# Master.net
KiCad netlist of a schematic drawn in Altium Designer
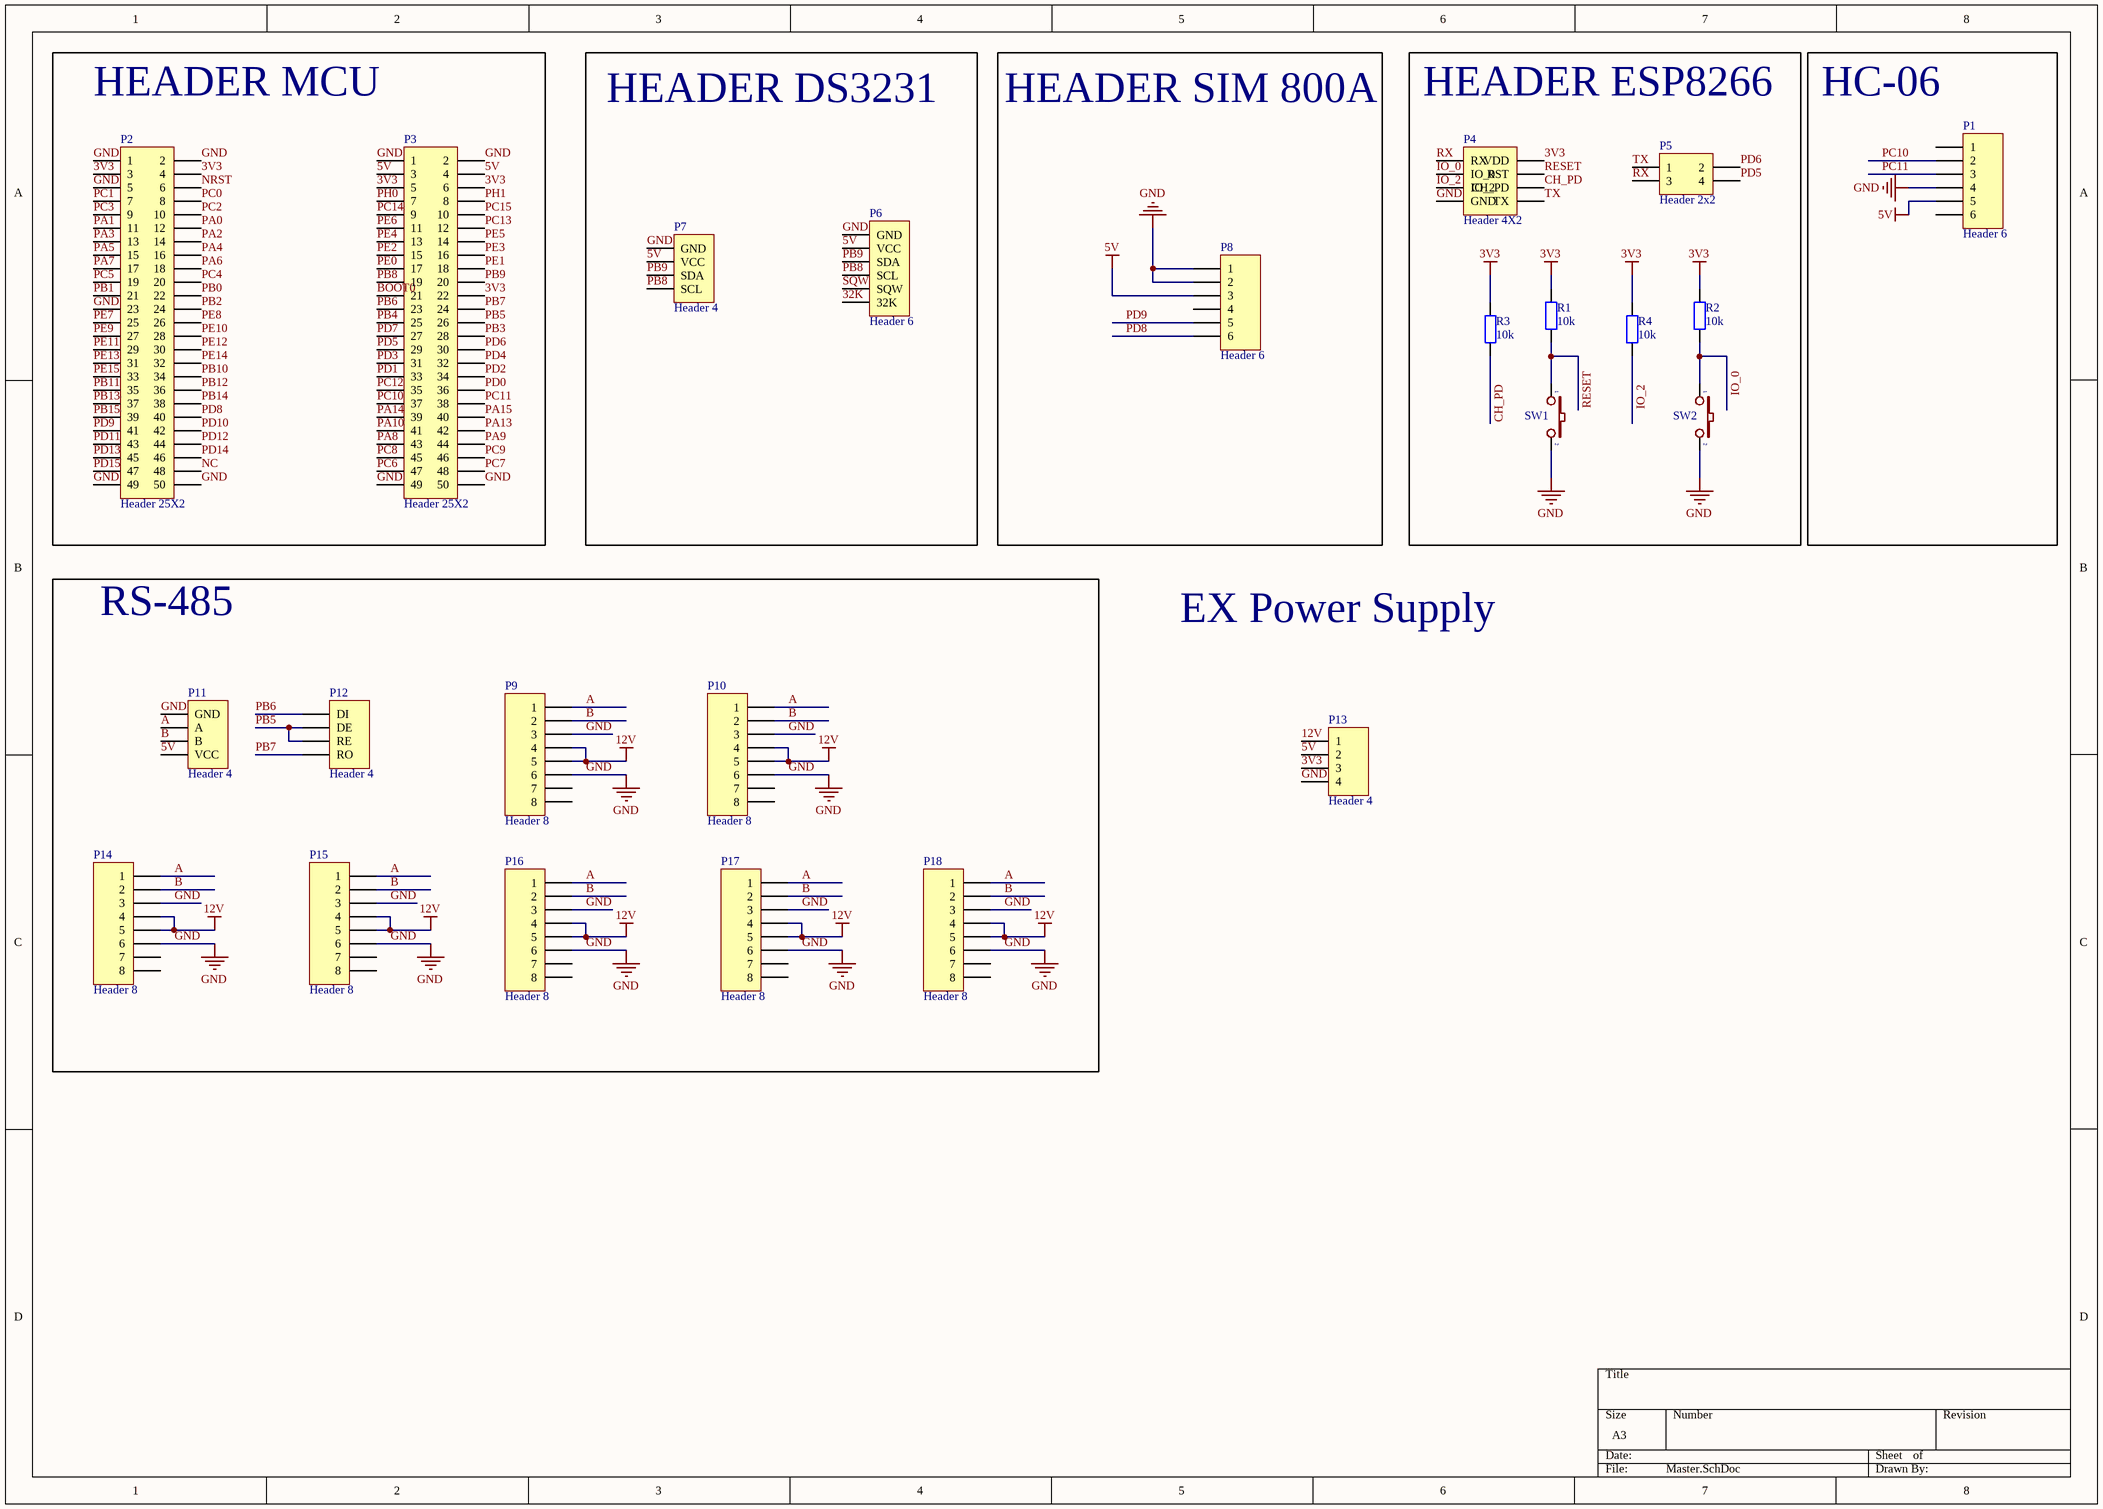
[diagram p0: Master.SchDoc]

(export (version "E")
  (design (tool "Eeschema 10.0.6"))
  (components
    (comp (ref "P1")
      (value "Header 6")
      (footprint "HDR1X6")
      (description "Header, 6-Pin")
      (fields (field (name "PUBLISHER") "Altium Limited"))
      (libsource (lib "THG") (part "Header 6"))
    )
    (comp (ref "P2")
      (value "Header 25X2")
      (footprint "HDR2X25")
      (description "Header, 25-Pin, Dual row")
      (fields (field (name "PUBLISHER") "Altium Limited"))
      (libsource (lib "Miscellaneous Connectors") (part "Header 25X2"))
    )
    (comp (ref "P3")
      (value "Header 25X2")
      (footprint "HDR2X25")
      (description "Header, 25-Pin, Dual row")
      (fields (field (name "PUBLISHER") "Altium Limited"))
      (libsource (lib "Miscellaneous Connectors") (part "Header 25X2"))
    )
    (comp (ref "P4")
      (value "Header 4X2")
      (footprint "HDR2X4")
      (description "Header, 4-Pin, Dual row")
      (fields (field (name "PUBLISHER") "Altium Limited"))
      (libsource (lib "Miscellaneous Connectors") (part "Header 4X2"))
    )
    (comp (ref "P5")
      (value "Header 2x2")
      (footprint "Header 2x2")
      (description "Header, 4-Pin, 2-Row")
      (fields (field (name "PUBLISHER") "Altium Limited"))
      (libsource (lib "hphonglib") (part "Header 2x2"))
    )
    (comp (ref "P6")
      (value "Header 6")
      (footprint "HDR1X6")
      (description "Header, 6-Pin")
      (fields (field (name "PUBLISHER") "Altium Limited"))
      (libsource (lib "Miscellaneous Connectors") (part "Header 6"))
    )
    (comp (ref "P7")
      (value "Header 4")
      (footprint "HDR1X4")
      (description "Header, 4-Pin")
      (fields (field (name "PUBLISHER") "Altium Limited"))
      (libsource (lib "Miscellaneous Connectors") (part "Header 4"))
    )
    (comp (ref "P8")
      (value "Header 6")
      (footprint "HDR1X6")
      (description "Header, 6-Pin")
      (fields (field (name "PUBLISHER") "Altium Limited"))
      (libsource (lib "Miscellaneous Connectors") (part "Header 6"))
    )
    (comp (ref "P9")
      (value "Header 8")
      (footprint "RJ11")
      (description "Header, 8-Pin")
      (fields (field (name "PUBLISHER") "Altium Limited"))
      (libsource (lib "THG") (part "Header 8"))
    )
    (comp (ref "P10")
      (value "Header 8")
      (footprint "RJ11")
      (description "Header, 8-Pin")
      (fields (field (name "PUBLISHER") "Altium Limited"))
      (libsource (lib "THG") (part "Header 8"))
    )
    (comp (ref "P11")
      (value "Header 4")
      (footprint "HDR1X4")
      (description "Header, 4-Pin")
      (fields (field (name "PUBLISHER") "Altium Limited"))
      (libsource (lib "Miscellaneous Connectors") (part "Header 4"))
    )
    (comp (ref "P12")
      (value "Header 4")
      (footprint "HDR1X4")
      (description "Header, 4-Pin")
      (fields (field (name "PUBLISHER") "Altium Limited"))
      (libsource (lib "Miscellaneous Connectors") (part "Header 4"))
    )
    (comp (ref "P13")
      (value "Header 4")
      (footprint "Header 4")
      (description "Header, 4-Pin")
      (fields (field (name "PUBLISHER") "Altium Limited"))
      (libsource (lib "hphonglib") (part "Header 4"))
    )
    (comp (ref "P14")
      (value "Header 8")
      (footprint "RJ11")
      (description "Header, 8-Pin")
      (fields (field (name "PUBLISHER") "Altium Limited"))
      (libsource (lib "THG") (part "Header 8"))
    )
    (comp (ref "P15")
      (value "Header 8")
      (footprint "RJ11")
      (description "Header, 8-Pin")
      (fields (field (name "PUBLISHER") "Altium Limited"))
      (libsource (lib "THG") (part "Header 8"))
    )
    (comp (ref "P16")
      (value "Header 8")
      (footprint "RJ11")
      (description "Header, 8-Pin")
      (fields (field (name "PUBLISHER") "Altium Limited"))
      (libsource (lib "THG") (part "Header 8"))
    )
    (comp (ref "P17")
      (value "Header 8")
      (footprint "RJ11")
      (description "Header, 8-Pin")
      (fields (field (name "PUBLISHER") "Altium Limited"))
      (libsource (lib "THG") (part "Header 8"))
    )
    (comp (ref "P18")
      (value "Header 8")
      (footprint "RJ11")
      (description "Header, 8-Pin")
      (fields (field (name "PUBLISHER") "Altium Limited"))
      (libsource (lib "THG") (part "Header 8"))
    )
    (comp (ref "R1")
      (value "10k")
      (footprint "R1/4W")
      (description "RES_0805")
      (fields (field (name "Comment") "RES_SMD_0805") (field (name "PUBLISHER") "Altium Limited"))
      (libsource (lib "THG") (part "RES_SMD_0805"))
    )
    (comp (ref "R2")
      (value "10k")
      (footprint "R1/4W")
      (description "RES_0805")
      (fields (field (name "Comment") "RES_SMD_0805") (field (name "PUBLISHER") "Altium Limited"))
      (libsource (lib "THG") (part "RES_SMD_0805"))
    )
    (comp (ref "R3")
      (value "10k")
      (footprint "R1/4W")
      (description "RES_0805")
      (fields (field (name "Comment") "RES_SMD_0805") (field (name "PUBLISHER") "Altium Limited"))
      (libsource (lib "THG") (part "RES_SMD_0805"))
    )
    (comp (ref "R4")
      (value "10k")
      (footprint "R1/4W")
      (description "RES_0805")
      (fields (field (name "Comment") "RES_SMD_0805") (field (name "PUBLISHER") "Altium Limited"))
      (libsource (lib "THG") (part "RES_SMD_0805"))
    )
    (comp (ref "SW1")
      (value "SW")
      (footprint "SW-SMD")
      (description "Switch button 2 pin")
      (libsource (lib "hphonglib") (part "SW2"))
    )
    (comp (ref "SW2")
      (value "SW")
      (footprint "SW-SMD")
      (description "Switch button 2 pin")
      (libsource (lib "hphonglib") (part "SW2"))
    )
  )
  (nets
    (net (code "1") (name "/32K") (class "Default")
      (node (ref "P6") (pin "6") (pinfunction "32K_6") (pintype "passive"))
    )
    (net (code "2") (name "/A") (class "Default")
      (node (ref "P10") (pin "1") (pinfunction "1_1") (pintype "passive"))
      (node (ref "P11") (pin "2") (pinfunction "VCC_2") (pintype "passive"))
      (node (ref "P14") (pin "1") (pinfunction "1_1") (pintype "passive"))
      (node (ref "P15") (pin "1") (pinfunction "1_1") (pintype "passive"))
      (node (ref "P16") (pin "1") (pinfunction "1_1") (pintype "passive"))
      (node (ref "P17") (pin "1") (pinfunction "1_1") (pintype "passive"))
      (node (ref "P18") (pin "1") (pinfunction "1_1") (pintype "passive"))
      (node (ref "P9") (pin "1") (pinfunction "1_1") (pintype "passive"))
    )
    (net (code "3") (name "/B") (class "Default")
      (node (ref "P10") (pin "2") (pinfunction "2_2") (pintype "passive"))
      (node (ref "P11") (pin "3") (pinfunction "SDA_3") (pintype "passive"))
      (node (ref "P14") (pin "2") (pinfunction "2_2") (pintype "passive"))
      (node (ref "P15") (pin "2") (pinfunction "2_2") (pintype "passive"))
      (node (ref "P16") (pin "2") (pinfunction "2_2") (pintype "passive"))
      (node (ref "P17") (pin "2") (pinfunction "2_2") (pintype "passive"))
      (node (ref "P18") (pin "2") (pinfunction "2_2") (pintype "passive"))
      (node (ref "P9") (pin "2") (pinfunction "2_2") (pintype "passive"))
    )
    (net (code "4") (name "/BOOT0") (class "Default")
      (node (ref "P3") (pin "21") (pinfunction "21_21") (pintype "passive"))
    )
    (net (code "5") (name "/CH_PD") (class "Default")
      (node (ref "P4") (pin "6") (pinfunction "CH_PD_6") (pintype "passive"))
      (node (ref "R3") (pin "2") (pinfunction "2_2") (pintype "passive"))
    )
    (net (code "6") (name "/IO_0") (class "Default")
      (node (ref "P4") (pin "3") (pinfunction "IO_0_3") (pintype "passive"))
      (node (ref "R2") (pin "2") (pinfunction "2_2") (pintype "passive"))
      (node (ref "SW2") (pin "1") (pinfunction "1_1") (pintype "passive"))
    )
    (net (code "7") (name "/IO_2") (class "Default")
      (node (ref "P4") (pin "5") (pinfunction "IO_2_5") (pintype "passive"))
      (node (ref "R4") (pin "2") (pinfunction "2_2") (pintype "passive"))
    )
    (net (code "8") (name "/NC") (class "Default")
      (node (ref "P2") (pin "48") (pinfunction "48_48") (pintype "passive"))
    )
    (net (code "9") (name "/NRST") (class "Default")
      (node (ref "P2") (pin "6") (pinfunction "6_6") (pintype "passive"))
    )
    (net (code "10") (name "/PA0") (class "Default")
      (node (ref "P2") (pin "12") (pinfunction "12_12") (pintype "passive"))
    )
    (net (code "11") (name "/PA1") (class "Default")
      (node (ref "P2") (pin "11") (pinfunction "11_11") (pintype "passive"))
    )
    (net (code "12") (name "/PA2") (class "Default")
      (node (ref "P2") (pin "14") (pinfunction "14_14") (pintype "passive"))
    )
    (net (code "13") (name "/PA3") (class "Default")
      (node (ref "P2") (pin "13") (pinfunction "13_13") (pintype "passive"))
    )
    (net (code "14") (name "/PA4") (class "Default")
      (node (ref "P2") (pin "16") (pinfunction "16_16") (pintype "passive"))
    )
    (net (code "15") (name "/PA5") (class "Default")
      (node (ref "P2") (pin "15") (pinfunction "15_15") (pintype "passive"))
    )
    (net (code "16") (name "/PA6") (class "Default")
      (node (ref "P2") (pin "18") (pinfunction "18_18") (pintype "passive"))
    )
    (net (code "17") (name "/PA7") (class "Default")
      (node (ref "P2") (pin "17") (pinfunction "17_17") (pintype "passive"))
    )
    (net (code "18") (name "/PA8") (class "Default")
      (node (ref "P3") (pin "43") (pinfunction "43_43") (pintype "passive"))
    )
    (net (code "19") (name "/PA9") (class "Default")
      (node (ref "P3") (pin "44") (pinfunction "44_44") (pintype "passive"))
    )
    (net (code "20") (name "/PA10") (class "Default")
      (node (ref "P3") (pin "41") (pinfunction "41_41") (pintype "passive"))
    )
    (net (code "21") (name "/PA13") (class "Default")
      (node (ref "P3") (pin "42") (pinfunction "42_42") (pintype "passive"))
    )
    (net (code "22") (name "/PA14") (class "Default")
      (node (ref "P3") (pin "39") (pinfunction "39_39") (pintype "passive"))
    )
    (net (code "23") (name "/PA15") (class "Default")
      (node (ref "P3") (pin "40") (pinfunction "40_40") (pintype "passive"))
    )
    (net (code "24") (name "/PB0") (class "Default")
      (node (ref "P2") (pin "22") (pinfunction "22_22") (pintype "passive"))
    )
    (net (code "25") (name "/PB1") (class "Default")
      (node (ref "P2") (pin "21") (pinfunction "21_21") (pintype "passive"))
    )
    (net (code "26") (name "/PB2") (class "Default")
      (node (ref "P2") (pin "24") (pinfunction "24_24") (pintype "passive"))
    )
    (net (code "27") (name "/PB3") (class "Default")
      (node (ref "P3") (pin "28") (pinfunction "28_28") (pintype "passive"))
    )
    (net (code "28") (name "/PB4") (class "Default")
      (node (ref "P3") (pin "25") (pinfunction "25_25") (pintype "passive"))
    )
    (net (code "29") (name "/PB5") (class "Default")
      (node (ref "P12") (pin "2") (pinfunction "VCC_2") (pintype "passive"))
      (node (ref "P12") (pin "3") (pinfunction "SDA_3") (pintype "passive"))
      (node (ref "P3") (pin "26") (pinfunction "26_26") (pintype "passive"))
    )
    (net (code "30") (name "/PB6") (class "Default")
      (node (ref "P12") (pin "1") (pinfunction "GND_1") (pintype "passive"))
      (node (ref "P3") (pin "23") (pinfunction "23_23") (pintype "passive"))
    )
    (net (code "31") (name "/PB7") (class "Default")
      (node (ref "P12") (pin "4") (pinfunction "SCL_4") (pintype "passive"))
      (node (ref "P3") (pin "24") (pinfunction "24_24") (pintype "passive"))
    )
    (net (code "32") (name "/PB8") (class "Default")
      (node (ref "P3") (pin "19") (pinfunction "19_19") (pintype "passive"))
      (node (ref "P6") (pin "4") (pinfunction "SCL_4") (pintype "passive"))
      (node (ref "P7") (pin "4") (pinfunction "SCL_4") (pintype "passive"))
    )
    (net (code "33") (name "/PB9") (class "Default")
      (node (ref "P3") (pin "20") (pinfunction "20_20") (pintype "passive"))
      (node (ref "P6") (pin "3") (pinfunction "SDA_3") (pintype "passive"))
      (node (ref "P7") (pin "3") (pinfunction "SDA_3") (pintype "passive"))
    )
    (net (code "34") (name "/PB10") (class "Default")
      (node (ref "P2") (pin "34") (pinfunction "34_34") (pintype "passive"))
    )
    (net (code "35") (name "/PB11") (class "Default")
      (node (ref "P2") (pin "35") (pinfunction "35_35") (pintype "passive"))
    )
    (net (code "36") (name "/PB12") (class "Default")
      (node (ref "P2") (pin "36") (pinfunction "36_36") (pintype "passive"))
    )
    (net (code "37") (name "/PB13") (class "Default")
      (node (ref "P2") (pin "37") (pinfunction "37_37") (pintype "passive"))
    )
    (net (code "38") (name "/PB14") (class "Default")
      (node (ref "P2") (pin "38") (pinfunction "38_38") (pintype "passive"))
    )
    (net (code "39") (name "/PB15") (class "Default")
      (node (ref "P2") (pin "39") (pinfunction "39_39") (pintype "passive"))
    )
    (net (code "40") (name "/PC0") (class "Default")
      (node (ref "P2") (pin "8") (pinfunction "8_8") (pintype "passive"))
    )
    (net (code "41") (name "/PC1") (class "Default")
      (node (ref "P2") (pin "7") (pinfunction "7_7") (pintype "passive"))
    )
    (net (code "42") (name "/PC2") (class "Default")
      (node (ref "P2") (pin "10") (pinfunction "10_10") (pintype "passive"))
    )
    (net (code "43") (name "/PC3") (class "Default")
      (node (ref "P2") (pin "9") (pinfunction "9_9") (pintype "passive"))
    )
    (net (code "44") (name "/PC4") (class "Default")
      (node (ref "P2") (pin "20") (pinfunction "20_20") (pintype "passive"))
    )
    (net (code "45") (name "/PC5") (class "Default")
      (node (ref "P2") (pin "19") (pinfunction "19_19") (pintype "passive"))
    )
    (net (code "46") (name "/PC6") (class "Default")
      (node (ref "P3") (pin "47") (pinfunction "47_47") (pintype "passive"))
    )
    (net (code "47") (name "/PC7") (class "Default")
      (node (ref "P3") (pin "48") (pinfunction "48_48") (pintype "passive"))
    )
    (net (code "48") (name "/PC8") (class "Default")
      (node (ref "P3") (pin "45") (pinfunction "45_45") (pintype "passive"))
    )
    (net (code "49") (name "/PC9") (class "Default")
      (node (ref "P3") (pin "46") (pinfunction "46_46") (pintype "passive"))
    )
    (net (code "50") (name "/PC10") (class "Default")
      (node (ref "P1") (pin "2") (pinfunction "2_2") (pintype "passive"))
      (node (ref "P3") (pin "37") (pinfunction "37_37") (pintype "passive"))
    )
    (net (code "51") (name "/PC11") (class "Default")
      (node (ref "P1") (pin "3") (pinfunction "3_3") (pintype "passive"))
      (node (ref "P3") (pin "38") (pinfunction "38_38") (pintype "passive"))
    )
    (net (code "52") (name "/PC12") (class "Default")
      (node (ref "P3") (pin "35") (pinfunction "35_35") (pintype "passive"))
    )
    (net (code "53") (name "/PC13") (class "Default")
      (node (ref "P3") (pin "12") (pinfunction "12_12") (pintype "passive"))
    )
    (net (code "54") (name "/PC14") (class "Default")
      (node (ref "P3") (pin "9") (pinfunction "9_9") (pintype "passive"))
    )
    (net (code "55") (name "/PC15") (class "Default")
      (node (ref "P3") (pin "10") (pinfunction "10_10") (pintype "passive"))
    )
    (net (code "56") (name "/PD0") (class "Default")
      (node (ref "P3") (pin "36") (pinfunction "36_36") (pintype "passive"))
    )
    (net (code "57") (name "/PD1") (class "Default")
      (node (ref "P3") (pin "33") (pinfunction "33_33") (pintype "passive"))
    )
    (net (code "58") (name "/PD2") (class "Default")
      (node (ref "P3") (pin "34") (pinfunction "34_34") (pintype "passive"))
    )
    (net (code "59") (name "/PD3") (class "Default")
      (node (ref "P3") (pin "31") (pinfunction "31_31") (pintype "passive"))
    )
    (net (code "60") (name "/PD4") (class "Default")
      (node (ref "P3") (pin "32") (pinfunction "32_32") (pintype "passive"))
    )
    (net (code "61") (name "/PD5") (class "Default")
      (node (ref "P3") (pin "29") (pinfunction "29_29") (pintype "passive"))
      (node (ref "P5") (pin "4") (pinfunction "4_4") (pintype "passive"))
    )
    (net (code "62") (name "/PD6") (class "Default")
      (node (ref "P3") (pin "30") (pinfunction "30_30") (pintype "passive"))
      (node (ref "P5") (pin "2") (pinfunction "2_2") (pintype "passive"))
    )
    (net (code "63") (name "/PD7") (class "Default")
      (node (ref "P3") (pin "27") (pinfunction "27_27") (pintype "passive"))
    )
    (net (code "64") (name "/PD8") (class "Default")
      (node (ref "P2") (pin "40") (pinfunction "40_40") (pintype "passive"))
      (node (ref "P8") (pin "6") (pinfunction "32K_6") (pintype "passive"))
    )
    (net (code "65") (name "/PD9") (class "Default")
      (node (ref "P2") (pin "41") (pinfunction "41_41") (pintype "passive"))
      (node (ref "P8") (pin "5") (pinfunction "SQW_5") (pintype "passive"))
    )
    (net (code "66") (name "/PD10") (class "Default")
      (node (ref "P2") (pin "42") (pinfunction "42_42") (pintype "passive"))
    )
    (net (code "67") (name "/PD11") (class "Default")
      (node (ref "P2") (pin "43") (pinfunction "43_43") (pintype "passive"))
    )
    (net (code "68") (name "/PD12") (class "Default")
      (node (ref "P2") (pin "44") (pinfunction "44_44") (pintype "passive"))
    )
    (net (code "69") (name "/PD13") (class "Default")
      (node (ref "P2") (pin "45") (pinfunction "45_45") (pintype "passive"))
    )
    (net (code "70") (name "/PD14") (class "Default")
      (node (ref "P2") (pin "46") (pinfunction "46_46") (pintype "passive"))
    )
    (net (code "71") (name "/PD15") (class "Default")
      (node (ref "P2") (pin "47") (pinfunction "47_47") (pintype "passive"))
    )
    (net (code "72") (name "/PE0") (class "Default")
      (node (ref "P3") (pin "17") (pinfunction "17_17") (pintype "passive"))
    )
    (net (code "73") (name "/PE1") (class "Default")
      (node (ref "P3") (pin "18") (pinfunction "18_18") (pintype "passive"))
    )
    (net (code "74") (name "/PE2") (class "Default")
      (node (ref "P3") (pin "15") (pinfunction "15_15") (pintype "passive"))
    )
    (net (code "75") (name "/PE3") (class "Default")
      (node (ref "P3") (pin "16") (pinfunction "16_16") (pintype "passive"))
    )
    (net (code "76") (name "/PE4") (class "Default")
      (node (ref "P3") (pin "13") (pinfunction "13_13") (pintype "passive"))
    )
    (net (code "77") (name "/PE5") (class "Default")
      (node (ref "P3") (pin "14") (pinfunction "14_14") (pintype "passive"))
    )
    (net (code "78") (name "/PE6") (class "Default")
      (node (ref "P3") (pin "11") (pinfunction "11_11") (pintype "passive"))
    )
    (net (code "79") (name "/PE7") (class "Default")
      (node (ref "P2") (pin "25") (pinfunction "25_25") (pintype "passive"))
    )
    (net (code "80") (name "/PE8") (class "Default")
      (node (ref "P2") (pin "26") (pinfunction "26_26") (pintype "passive"))
    )
    (net (code "81") (name "/PE9") (class "Default")
      (node (ref "P2") (pin "27") (pinfunction "27_27") (pintype "passive"))
    )
    (net (code "82") (name "/PE10") (class "Default")
      (node (ref "P2") (pin "28") (pinfunction "28_28") (pintype "passive"))
    )
    (net (code "83") (name "/PE11") (class "Default")
      (node (ref "P2") (pin "29") (pinfunction "29_29") (pintype "passive"))
    )
    (net (code "84") (name "/PE12") (class "Default")
      (node (ref "P2") (pin "30") (pinfunction "30_30") (pintype "passive"))
    )
    (net (code "85") (name "/PE13") (class "Default")
      (node (ref "P2") (pin "31") (pinfunction "31_31") (pintype "passive"))
    )
    (net (code "86") (name "/PE14") (class "Default")
      (node (ref "P2") (pin "32") (pinfunction "32_32") (pintype "passive"))
    )
    (net (code "87") (name "/PE15") (class "Default")
      (node (ref "P2") (pin "33") (pinfunction "33_33") (pintype "passive"))
    )
    (net (code "88") (name "/PH0") (class "Default")
      (node (ref "P3") (pin "7") (pinfunction "7_7") (pintype "passive"))
    )
    (net (code "89") (name "/PH1") (class "Default")
      (node (ref "P3") (pin "8") (pinfunction "8_8") (pintype "passive"))
    )
    (net (code "90") (name "/RESET") (class "Default")
      (node (ref "P4") (pin "4") (pinfunction "RST_4") (pintype "passive"))
      (node (ref "R1") (pin "2") (pinfunction "2_2") (pintype "passive"))
      (node (ref "SW1") (pin "1") (pinfunction "1_1") (pintype "passive"))
    )
    (net (code "91") (name "/RX") (class "Default")
      (node (ref "P4") (pin "1") (pinfunction "RX_1") (pintype "passive"))
      (node (ref "P5") (pin "3") (pinfunction "3_3") (pintype "passive"))
    )
    (net (code "92") (name "/SQW") (class "Default")
      (node (ref "P6") (pin "5") (pinfunction "SQW_5") (pintype "passive"))
    )
    (net (code "93") (name "/TX") (class "Default")
      (node (ref "P4") (pin "8") (pinfunction "TX_8") (pintype "passive"))
      (node (ref "P5") (pin "1") (pinfunction "1_1") (pintype "passive"))
    )
    (net (code "94") (name "3V3") (class "Default")
      (node (ref "P13") (pin "3") (pinfunction "3_3") (pintype "passive"))
      (node (ref "P2") (pin "3") (pinfunction "3_3") (pintype "passive"))
      (node (ref "P2") (pin "4") (pinfunction "4_4") (pintype "passive"))
      (node (ref "P3") (pin "22") (pinfunction "22_22") (pintype "passive"))
      (node (ref "P3") (pin "5") (pinfunction "5_5") (pintype "passive"))
      (node (ref "P3") (pin "6") (pinfunction "6_6") (pintype "passive"))
      (node (ref "P4") (pin "2") (pinfunction "VDD_2") (pintype "passive"))
      (node (ref "R1") (pin "1") (pinfunction "1_1") (pintype "passive"))
      (node (ref "R2") (pin "1") (pinfunction "1_1") (pintype "passive"))
      (node (ref "R3") (pin "1") (pinfunction "1_1") (pintype "passive"))
      (node (ref "R4") (pin "1") (pinfunction "1_1") (pintype "passive"))
    )
    (net (code "95") (name "5V") (class "Default")
      (node (ref "P1") (pin "5") (pinfunction "5_5") (pintype "passive"))
      (node (ref "P11") (pin "4") (pinfunction "SCL_4") (pintype "passive"))
      (node (ref "P13") (pin "2") (pinfunction "2_2") (pintype "passive"))
      (node (ref "P3") (pin "3") (pinfunction "3_3") (pintype "passive"))
      (node (ref "P3") (pin "4") (pinfunction "4_4") (pintype "passive"))
      (node (ref "P6") (pin "2") (pinfunction "VCC_2") (pintype "passive"))
      (node (ref "P7") (pin "2") (pinfunction "VCC_2") (pintype "passive"))
      (node (ref "P8") (pin "3") (pinfunction "SDA_3") (pintype "passive"))
    )
    (net (code "96") (name "12V") (class "Default")
      (node (ref "P10") (pin "4") (pinfunction "4_4") (pintype "passive"))
      (node (ref "P10") (pin "5") (pinfunction "5_5") (pintype "passive"))
      (node (ref "P13") (pin "1") (pinfunction "1_1") (pintype "passive"))
      (node (ref "P14") (pin "4") (pinfunction "4_4") (pintype "passive"))
      (node (ref "P14") (pin "5") (pinfunction "5_5") (pintype "passive"))
      (node (ref "P15") (pin "4") (pinfunction "4_4") (pintype "passive"))
      (node (ref "P15") (pin "5") (pinfunction "5_5") (pintype "passive"))
      (node (ref "P16") (pin "4") (pinfunction "4_4") (pintype "passive"))
      (node (ref "P16") (pin "5") (pinfunction "5_5") (pintype "passive"))
      (node (ref "P17") (pin "4") (pinfunction "4_4") (pintype "passive"))
      (node (ref "P17") (pin "5") (pinfunction "5_5") (pintype "passive"))
      (node (ref "P18") (pin "4") (pinfunction "4_4") (pintype "passive"))
      (node (ref "P18") (pin "5") (pinfunction "5_5") (pintype "passive"))
      (node (ref "P9") (pin "4") (pinfunction "4_4") (pintype "passive"))
      (node (ref "P9") (pin "5") (pinfunction "5_5") (pintype "passive"))
    )
    (net (code "97") (name "GND") (class "Default")
      (node (ref "P1") (pin "4") (pinfunction "4_4") (pintype "passive"))
      (node (ref "P10") (pin "3") (pinfunction "3_3") (pintype "passive"))
      (node (ref "P10") (pin "6") (pinfunction "6_6") (pintype "passive"))
      (node (ref "P11") (pin "1") (pinfunction "GND_1") (pintype "passive"))
      (node (ref "P13") (pin "4") (pinfunction "4_4") (pintype "passive"))
      (node (ref "P14") (pin "3") (pinfunction "3_3") (pintype "passive"))
      (node (ref "P14") (pin "6") (pinfunction "6_6") (pintype "passive"))
      (node (ref "P15") (pin "3") (pinfunction "3_3") (pintype "passive"))
      (node (ref "P15") (pin "6") (pinfunction "6_6") (pintype "passive"))
      (node (ref "P16") (pin "3") (pinfunction "3_3") (pintype "passive"))
      (node (ref "P16") (pin "6") (pinfunction "6_6") (pintype "passive"))
      (node (ref "P17") (pin "3") (pinfunction "3_3") (pintype "passive"))
      (node (ref "P17") (pin "6") (pinfunction "6_6") (pintype "passive"))
      (node (ref "P18") (pin "3") (pinfunction "3_3") (pintype "passive"))
      (node (ref "P18") (pin "6") (pinfunction "6_6") (pintype "passive"))
      (node (ref "P2") (pin "1") (pinfunction "1_1") (pintype "passive"))
      (node (ref "P2") (pin "2") (pinfunction "2_2") (pintype "passive"))
      (node (ref "P2") (pin "23") (pinfunction "23_23") (pintype "passive"))
      (node (ref "P2") (pin "49") (pinfunction "49_49") (pintype "passive"))
      (node (ref "P2") (pin "5") (pinfunction "5_5") (pintype "passive"))
      (node (ref "P2") (pin "50") (pinfunction "50_50") (pintype "passive"))
      (node (ref "P3") (pin "1") (pinfunction "1_1") (pintype "passive"))
      (node (ref "P3") (pin "2") (pinfunction "2_2") (pintype "passive"))
      (node (ref "P3") (pin "49") (pinfunction "49_49") (pintype "passive"))
      (node (ref "P3") (pin "50") (pinfunction "50_50") (pintype "passive"))
      (node (ref "P4") (pin "7") (pinfunction "GND_7") (pintype "passive"))
      (node (ref "P6") (pin "1") (pinfunction "GND_1") (pintype "passive"))
      (node (ref "P7") (pin "1") (pinfunction "GND_1") (pintype "passive"))
      (node (ref "P8") (pin "1") (pinfunction "GND_1") (pintype "passive"))
      (node (ref "P8") (pin "2") (pinfunction "VCC_2") (pintype "passive"))
      (node (ref "P9") (pin "3") (pinfunction "3_3") (pintype "passive"))
      (node (ref "P9") (pin "6") (pinfunction "6_6") (pintype "passive"))
      (node (ref "SW1") (pin "2") (pinfunction "2_2") (pintype "passive"))
      (node (ref "SW2") (pin "2") (pinfunction "2_2") (pintype "passive"))
    )
    (net (code "98") (name "unconnected-(P1-Pad1)") (class "Default")
      (node (ref "P1") (pin "1") (pinfunction "1_1") (pintype "passive"))
    )
    (net (code "99") (name "unconnected-(P1-Pad6)") (class "Default")
      (node (ref "P1") (pin "6") (pinfunction "6_6") (pintype "passive"))
    )
    (net (code "100") (name "unconnected-(P8-SCL-Pad4)") (class "Default")
      (node (ref "P8") (pin "4") (pinfunction "SCL_4") (pintype "passive"))
    )
    (net (code "101") (name "unconnected-(P9-Pad7)") (class "Default")
      (node (ref "P9") (pin "7") (pinfunction "7_7") (pintype "passive"))
    )
    (net (code "102") (name "unconnected-(P9-Pad8)") (class "Default")
      (node (ref "P9") (pin "8") (pinfunction "8_8") (pintype "passive"))
    )
    (net (code "103") (name "unconnected-(P10-Pad7)") (class "Default")
      (node (ref "P10") (pin "7") (pinfunction "7_7") (pintype "passive"))
    )
    (net (code "104") (name "unconnected-(P10-Pad8)") (class "Default")
      (node (ref "P10") (pin "8") (pinfunction "8_8") (pintype "passive"))
    )
    (net (code "105") (name "unconnected-(P14-Pad7)") (class "Default")
      (node (ref "P14") (pin "7") (pinfunction "7_7") (pintype "passive"))
    )
    (net (code "106") (name "unconnected-(P14-Pad8)") (class "Default")
      (node (ref "P14") (pin "8") (pinfunction "8_8") (pintype "passive"))
    )
    (net (code "107") (name "unconnected-(P15-Pad7)") (class "Default")
      (node (ref "P15") (pin "7") (pinfunction "7_7") (pintype "passive"))
    )
    (net (code "108") (name "unconnected-(P15-Pad8)") (class "Default")
      (node (ref "P15") (pin "8") (pinfunction "8_8") (pintype "passive"))
    )
    (net (code "109") (name "unconnected-(P16-Pad7)") (class "Default")
      (node (ref "P16") (pin "7") (pinfunction "7_7") (pintype "passive"))
    )
    (net (code "110") (name "unconnected-(P16-Pad8)") (class "Default")
      (node (ref "P16") (pin "8") (pinfunction "8_8") (pintype "passive"))
    )
    (net (code "111") (name "unconnected-(P17-Pad7)") (class "Default")
      (node (ref "P17") (pin "7") (pinfunction "7_7") (pintype "passive"))
    )
    (net (code "112") (name "unconnected-(P17-Pad8)") (class "Default")
      (node (ref "P17") (pin "8") (pinfunction "8_8") (pintype "passive"))
    )
    (net (code "113") (name "unconnected-(P18-Pad7)") (class "Default")
      (node (ref "P18") (pin "7") (pinfunction "7_7") (pintype "passive"))
    )
    (net (code "114") (name "unconnected-(P18-Pad8)") (class "Default")
      (node (ref "P18") (pin "8") (pinfunction "8_8") (pintype "passive"))
    )
  )
)
